# pwm-tl494-smd.net
KiCad netlist of a schematic drawn in Altium Designer
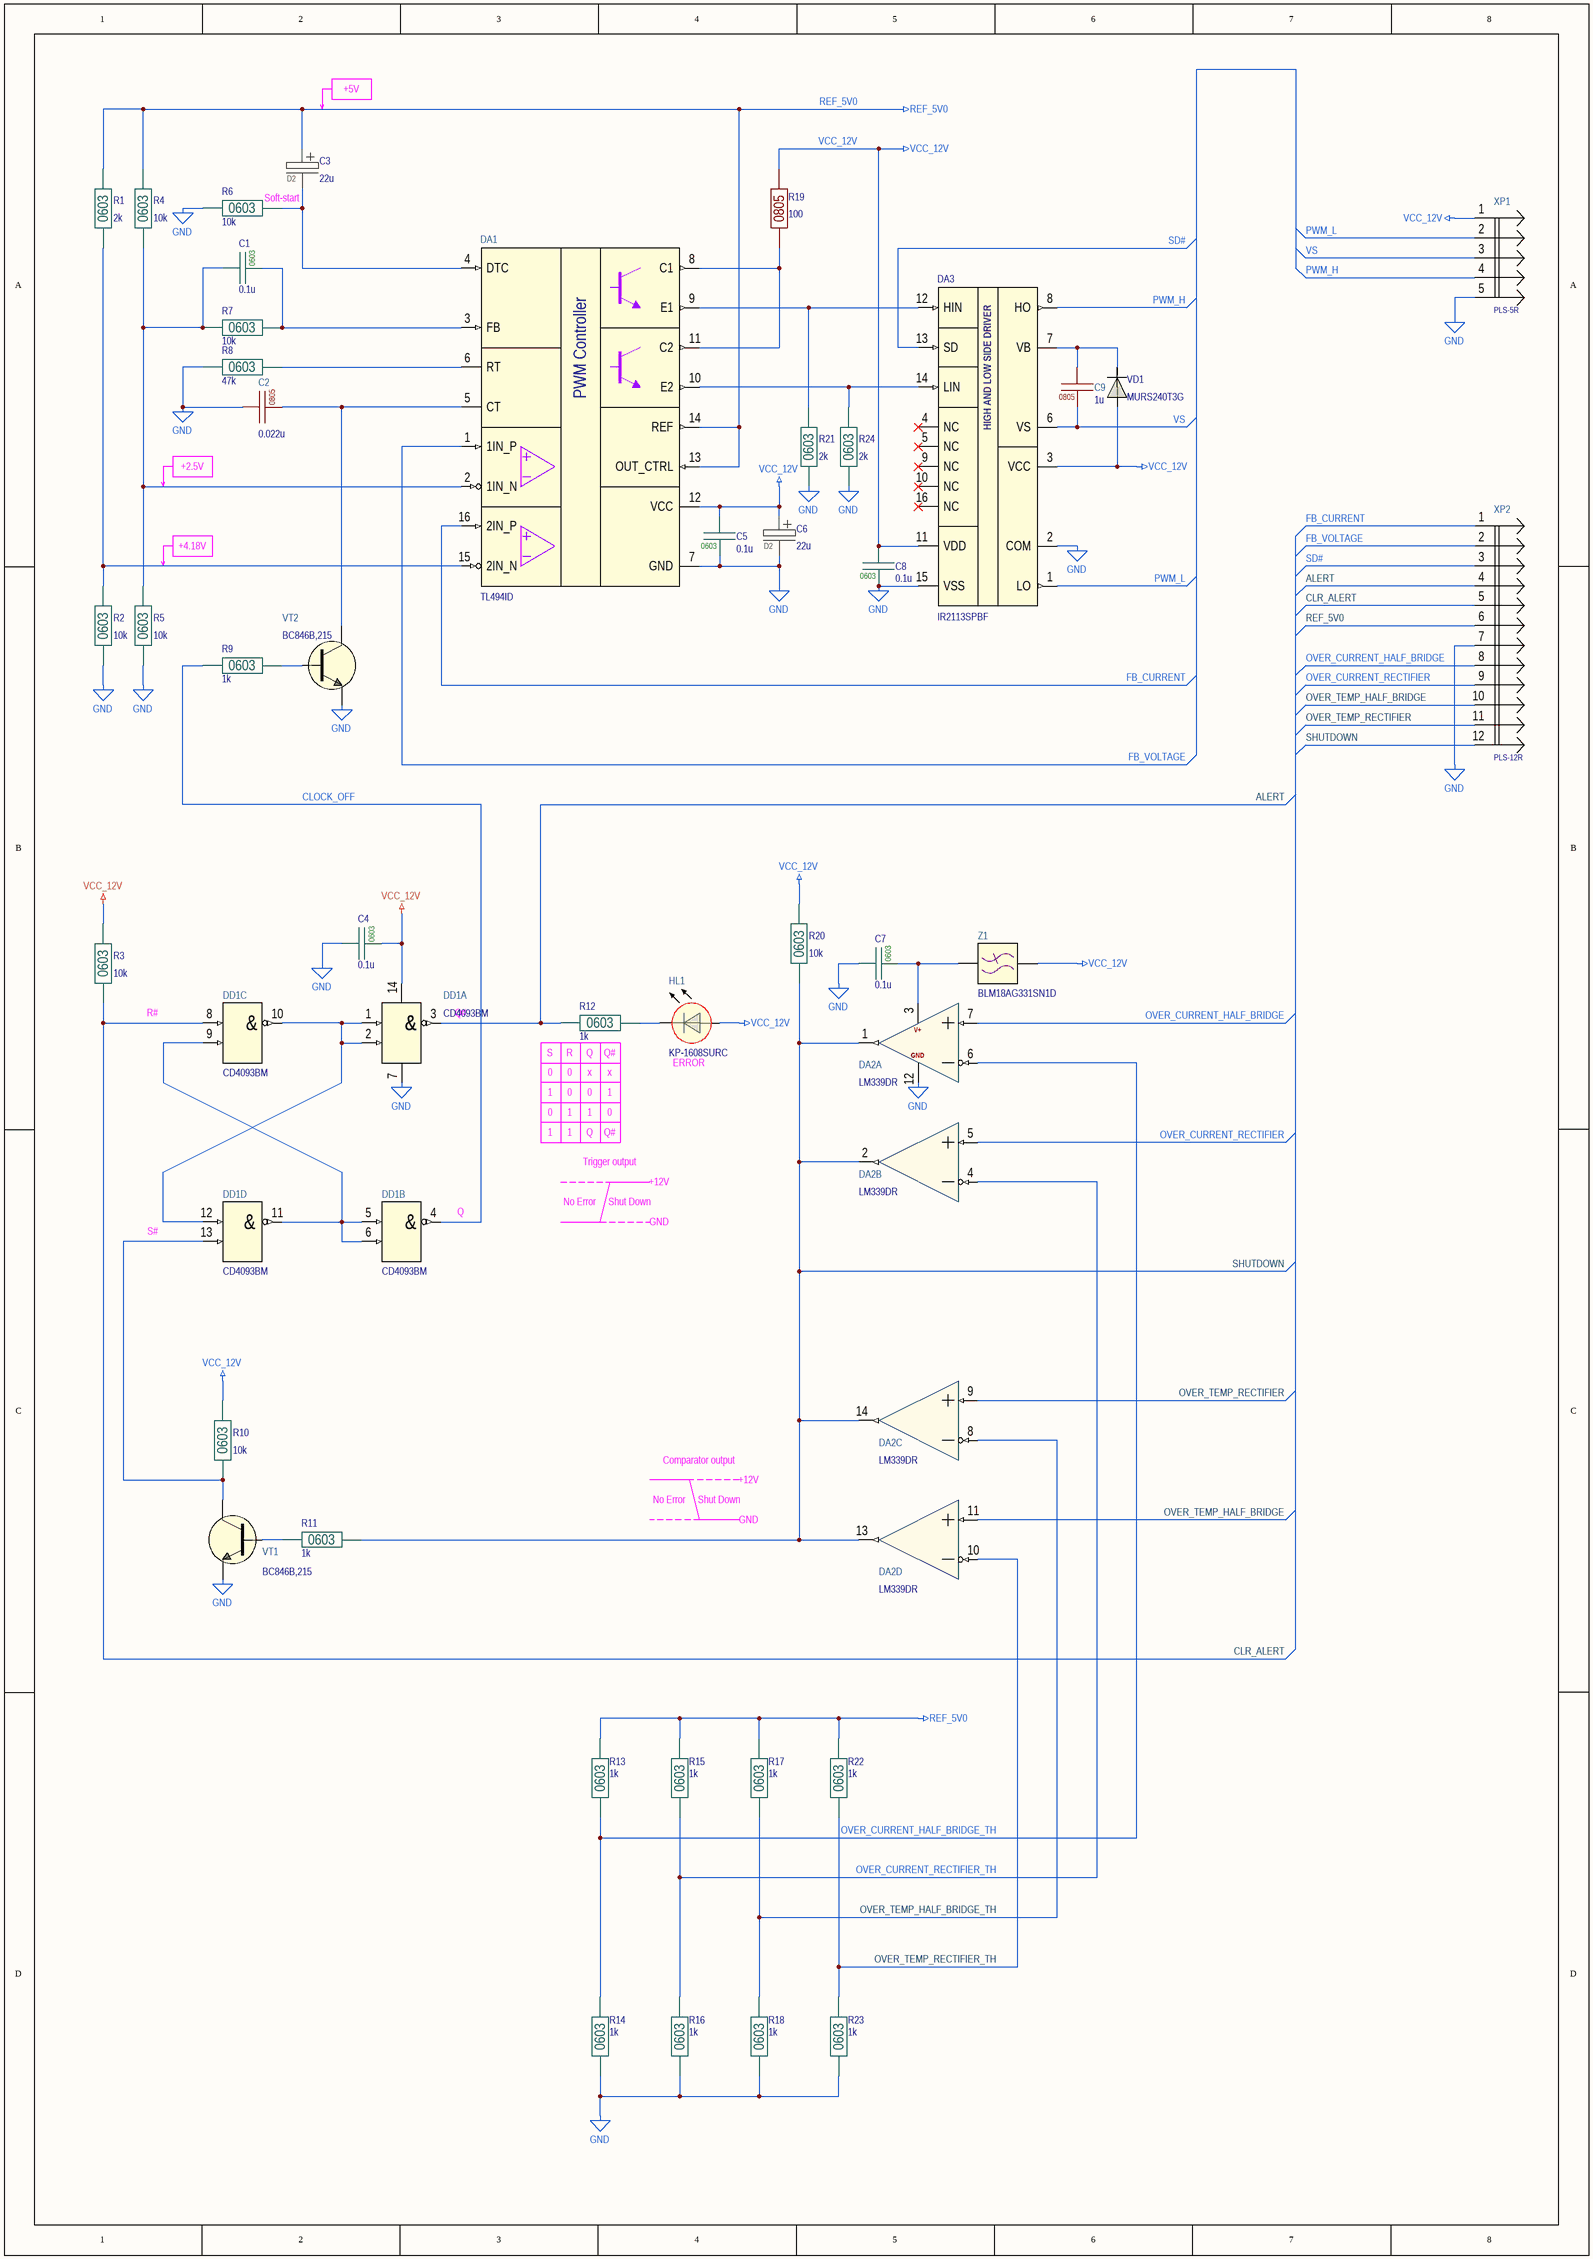
[diagram p0: pwm-tl494-smd.SchDoc]

(export (version "E")
  (design (tool "Eeschema 10.0.6"))
  (components
    (comp (ref "C1")
      (value "0.1u")
      (footprint "PcbLib_RC:CAP0603")
      (description "Capacitors 0603 package case")
      (fields
        (field (name "TOLERANCE") "± 10 %")
        (field (name "VOLTAGE") "50V")
        (field (name "PACKAGE") "0603")
      )
      (libsource (lib "Schlib_RC") (part "C0603"))
    )
    (comp (ref "C2")
      (value "0.022u")
      (footprint "PcbLib_RC:CAP0805-0.95")
      (description "Capacitors 0805 package case")
      (fields
        (field (name "TOLERANCE") "± 5 %")
        (field (name "VOLTAGE") "50V")
        (field (name "PACKAGE") "0805")
      )
      (libsource (lib "Schlib_RC") (part "C0805"))
    )
    (comp (ref "C3")
      (value "22u")
      (footprint "PcbLib_RC:CAP_TQC_D2")
      (description "Conductive Polymer Tantalum Solid Capacitors TQC-Series. Case code D2")
      (fields
        (field (name "TOLERANCE") "± 20 %")
        (field (name "PART NUMBER") "25TQC22MV")
        (field (name "PACKAGE") "D2")
      )
      (libsource (lib "Schlib_RC") (part "C_TQC_D2"))
    )
    (comp (ref "C4")
      (value "0.1u")
      (footprint "PcbLib_RC:CAP0603")
      (description "Capacitors 0603 package case")
      (fields
        (field (name "TOLERANCE") "± 10 %")
        (field (name "VOLTAGE") "50V")
        (field (name "PACKAGE") "0603")
      )
      (libsource (lib "Schlib_RC") (part "C0603"))
    )
    (comp (ref "C5")
      (value "0.1u")
      (footprint "PcbLib_RC:CAP0603")
      (description "Capacitors 0603 package case")
      (fields
        (field (name "TOLERANCE") "± 10 %")
        (field (name "VOLTAGE") "50V")
        (field (name "PACKAGE") "0603")
      )
      (libsource (lib "Schlib_RC") (part "C0603"))
    )
    (comp (ref "C6")
      (value "22u")
      (footprint "PcbLib_RC:CAP_TQC_D2")
      (description "Conductive Polymer Tantalum Solid Capacitors TQC-Series. Case code D2")
      (fields
        (field (name "TOLERANCE") "± 20 %")
        (field (name "PART NUMBER") "25TQC22MV")
        (field (name "PACKAGE") "D2")
      )
      (libsource (lib "Schlib_RC") (part "C_TQC_D2"))
    )
    (comp (ref "C7")
      (value "0.1u")
      (footprint "PcbLib_RC:CAP0603")
      (description "Capacitors 0603 package case")
      (fields
        (field (name "TOLERANCE") "± 10 %")
        (field (name "VOLTAGE") "50V")
        (field (name "PACKAGE") "0603")
      )
      (libsource (lib "Schlib_RC") (part "C0603"))
    )
    (comp (ref "C8")
      (value "0.1u")
      (footprint "PcbLib_RC:CAP0603")
      (description "Capacitors 0603 package case")
      (fields
        (field (name "TOLERANCE") "± 10 %")
        (field (name "VOLTAGE") "50V")
        (field (name "PACKAGE") "0603")
      )
      (libsource (lib "Schlib_RC") (part "C0603"))
    )
    (comp (ref "C9")
      (value "1u")
      (footprint "PcbLib_RC:CAP0805-1.35")
      (description "Capacitors 0805 package case")
      (fields
        (field (name "TOLERANCE") "± 10 %")
        (field (name "VOLTAGE") "50V")
        (field (name "PACKAGE") "0805")
      )
      (libsource (lib "Schlib_RC") (part "C0805"))
    )
    (comp (ref "DA1")
      (value "TL494ID")
      (footprint "PcbLib_ICs:SOIC-16")
      (description "Pulse-Width-Modulation Control Circuits")
      (fields (field (name "MANUFACTURER") "Texas Instruments"))
      (libsource (lib "Schlib_Texas_Instruments") (part "TL494ID"))
    )
    (comp (ref "DA2")
      (value "LM339DR")
      (footprint "PcbLib_ICs:SOIC-14")
      (description "Quad Comparators")
      (fields (field (name "MANUFACTURER") "Texas Instruments"))
      (libsource (lib "Schlib_Texas_Instruments") (part "LM339DR"))
    )
    (comp (ref "DA3")
      (value "IR2113SPBF")
      (footprint "PcbLib_ICs:SO-16W")
      (description "HIGH AND LOW SIDE DRIVER")
      (fields (field (name "MANUFACTURER") "International Rectifier"))
      (libsource (lib "Schlib_Infineon") (part "IR2113SPBF"))
    )
    (comp (ref "DD1")
      (value "CD4093BM")
      (footprint "PcbLib_ICs:SOIC-14")
      (description "Quad 2-Input NAND Gate Schmitt Triggers")
      (fields (field (name "MANUFACTURER") "Texas Instruments"))
      (libsource (lib "Schlib_Texas_Instruments") (part "CD4093BM"))
    )
    (comp (ref "HL1")
      (value "KP-1608SURC")
      (footprint "PcbLib_Others:LED0603R")
      (description "Hyper red led (package case 0603)")
      (fields (field (name "MANUFACTURER") "Kingbright Company LLC."))
      (libsource (lib "Schlib_Kingbright") (part "KP-1608SURC"))
    )
    (comp (ref "R1")
      (value "2k")
      (footprint "PcbLib_RC:RES0603B")
      (description "Resistor 0603 package case")
      (fields
        (field (name "TOLERANCE") "± 1 %")
        (field (name "PART NUMBER") "RC0603FR-072KL")
        (field (name "PACKAGE") "0603")
      )
      (libsource (lib "Schlib_RC") (part "R0603"))
    )
    (comp (ref "R2")
      (value "10k")
      (footprint "PcbLib_RC:RES0603B")
      (description "Resistor 0603 package case")
      (fields
        (field (name "TOLERANCE") "± 1 %")
        (field (name "PART NUMBER") "RC0603FR-0710KL")
        (field (name "PACKAGE") "0603")
      )
      (libsource (lib "Schlib_RC") (part "R0603"))
    )
    (comp (ref "R3")
      (value "10k")
      (footprint "PcbLib_RC:RES0603B")
      (description "Resistor 0603 package case")
      (fields
        (field (name "TOLERANCE") "± 1 %")
        (field (name "PART NUMBER") "RC0603FR-0710KL")
        (field (name "PACKAGE") "0603")
      )
      (libsource (lib "Schlib_RC") (part "R0603"))
    )
    (comp (ref "R4")
      (value "10k")
      (footprint "PcbLib_RC:RES0603B")
      (description "Resistor 0603 package case")
      (fields
        (field (name "TOLERANCE") "± 1 %")
        (field (name "PART NUMBER") "RC0603FR-0710KL")
        (field (name "PACKAGE") "0603")
      )
      (libsource (lib "Schlib_RC") (part "R0603"))
    )
    (comp (ref "R5")
      (value "10k")
      (footprint "PcbLib_RC:RES0603B")
      (description "Resistor 0603 package case")
      (fields
        (field (name "TOLERANCE") "± 1 %")
        (field (name "PART NUMBER") "RC0603FR-0710KL")
        (field (name "PACKAGE") "0603")
      )
      (libsource (lib "Schlib_RC") (part "R0603"))
    )
    (comp (ref "R6")
      (value "10k")
      (footprint "PcbLib_RC:RES0603B")
      (description "Resistor 0603 package case")
      (fields
        (field (name "TOLERANCE") "± 1 %")
        (field (name "PART NUMBER") "RC0603FR-0710KL")
        (field (name "PACKAGE") "0603")
      )
      (libsource (lib "Schlib_RC") (part "R0603"))
    )
    (comp (ref "R7")
      (value "10k")
      (footprint "PcbLib_RC:RES0603B")
      (description "Resistor 0603 package case")
      (fields
        (field (name "TOLERANCE") "± 1 %")
        (field (name "PART NUMBER") "RC0603FR-0710KL")
        (field (name "PACKAGE") "0603")
      )
      (libsource (lib "Schlib_RC") (part "R0603"))
    )
    (comp (ref "R8")
      (value "47k")
      (footprint "PcbLib_RC:RES0603B")
      (description "Resistor 0603 package case")
      (fields
        (field (name "TOLERANCE") "± 1 %")
        (field (name "PART NUMBER") "RC0603FR-0747KL")
        (field (name "PACKAGE") "0603")
      )
      (libsource (lib "Schlib_RC") (part "R0603"))
    )
    (comp (ref "R9")
      (value "1k")
      (footprint "PcbLib_RC:RES0603B")
      (description "Resistor 0603 package case")
      (fields
        (field (name "TOLERANCE") "± 1 %")
        (field (name "PART NUMBER") "RC0603FR-071KL")
        (field (name "PACKAGE") "0603")
      )
      (libsource (lib "Schlib_RC") (part "R0603"))
    )
    (comp (ref "R10")
      (value "10k")
      (footprint "PcbLib_RC:RES0603B")
      (description "Resistor 0603 package case")
      (fields
        (field (name "TOLERANCE") "± 1 %")
        (field (name "PART NUMBER") "RC0603FR-0710KL")
        (field (name "PACKAGE") "0603")
      )
      (libsource (lib "Schlib_RC") (part "R0603"))
    )
    (comp (ref "R11")
      (value "1k")
      (footprint "PcbLib_RC:RES0603B")
      (description "Resistor 0603 package case")
      (fields
        (field (name "TOLERANCE") "± 1 %")
        (field (name "PART NUMBER") "RC0603FR-071KL")
        (field (name "PACKAGE") "0603")
      )
      (libsource (lib "Schlib_RC") (part "R0603"))
    )
    (comp (ref "R12")
      (value "1k")
      (footprint "PcbLib_RC:RES0603B")
      (description "Resistor 0603 package case")
      (fields
        (field (name "TOLERANCE") "± 1 %")
        (field (name "PART NUMBER") "RC0603FR-071KL")
        (field (name "PACKAGE") "0603")
      )
      (libsource (lib "Schlib_RC") (part "R0603"))
    )
    (comp (ref "R13")
      (value "1k")
      (footprint "PcbLib_RC:RES0603B")
      (description "Resistor 0603 package case")
      (fields
        (field (name "TOLERANCE") "± 1 %")
        (field (name "PART NUMBER") "RC0603FR-071KL")
        (field (name "PACKAGE") "0603")
      )
      (libsource (lib "Schlib_RC") (part "R0603"))
    )
    (comp (ref "R14")
      (value "1k")
      (footprint "PcbLib_RC:RES0603B")
      (description "Resistor 0603 package case")
      (fields
        (field (name "TOLERANCE") "± 1 %")
        (field (name "PART NUMBER") "RC0603FR-071KL")
        (field (name "PACKAGE") "0603")
      )
      (libsource (lib "Schlib_RC") (part "R0603"))
    )
    (comp (ref "R15")
      (value "1k")
      (footprint "PcbLib_RC:RES0603B")
      (description "Resistor 0603 package case")
      (fields
        (field (name "TOLERANCE") "± 1 %")
        (field (name "PART NUMBER") "RC0603FR-071KL")
        (field (name "PACKAGE") "0603")
      )
      (libsource (lib "Schlib_RC") (part "R0603"))
    )
    (comp (ref "R16")
      (value "1k")
      (footprint "PcbLib_RC:RES0603B")
      (description "Resistor 0603 package case")
      (fields
        (field (name "TOLERANCE") "± 1 %")
        (field (name "PART NUMBER") "RC0603FR-071KL")
        (field (name "PACKAGE") "0603")
      )
      (libsource (lib "Schlib_RC") (part "R0603"))
    )
    (comp (ref "R17")
      (value "1k")
      (footprint "PcbLib_RC:RES0603B")
      (description "Resistor 0603 package case")
      (fields
        (field (name "TOLERANCE") "± 1 %")
        (field (name "PART NUMBER") "RC0603FR-071KL")
        (field (name "PACKAGE") "0603")
      )
      (libsource (lib "Schlib_RC") (part "R0603"))
    )
    (comp (ref "R18")
      (value "1k")
      (footprint "PcbLib_RC:RES0603B")
      (description "Resistor 0603 package case")
      (fields
        (field (name "TOLERANCE") "± 1 %")
        (field (name "PART NUMBER") "RC0603FR-071KL")
        (field (name "PACKAGE") "0603")
      )
      (libsource (lib "Schlib_RC") (part "R0603"))
    )
    (comp (ref "R19")
      (value "100")
      (footprint "PcbLib_RC:RES0805B")
      (description "Resistor 0805 package case")
      (fields
        (field (name "TOLERANCE") "± 1 %")
        (field (name "PART NUMBER") "RC0805FR-07100RL")
        (field (name "PACKAGE") "0805")
      )
      (libsource (lib "Schlib_RC") (part "R0805"))
    )
    (comp (ref "R20")
      (value "10k")
      (footprint "PcbLib_RC:RES0603B")
      (description "Resistor 0603 package case")
      (fields
        (field (name "TOLERANCE") "± 1 %")
        (field (name "PART NUMBER") "RC0603FR-0710KL")
        (field (name "PACKAGE") "0603")
      )
      (libsource (lib "Schlib_RC") (part "R0603"))
    )
    (comp (ref "R21")
      (value "2k")
      (footprint "PcbLib_RC:RES0603B")
      (description "Resistor 0603 package case")
      (fields
        (field (name "TOLERANCE") "± 1 %")
        (field (name "PART NUMBER") "RC0603FR-072KL")
        (field (name "PACKAGE") "0603")
      )
      (libsource (lib "Schlib_RC") (part "R0603"))
    )
    (comp (ref "R22")
      (value "1k")
      (footprint "PcbLib_RC:RES0603B")
      (description "Resistor 0603 package case")
      (fields
        (field (name "TOLERANCE") "± 1 %")
        (field (name "PART NUMBER") "RC0603FR-071KL")
        (field (name "PACKAGE") "0603")
      )
      (libsource (lib "Schlib_RC") (part "R0603"))
    )
    (comp (ref "R23")
      (value "1k")
      (footprint "PcbLib_RC:RES0603B")
      (description "Resistor 0603 package case")
      (fields
        (field (name "TOLERANCE") "± 1 %")
        (field (name "PART NUMBER") "RC0603FR-071KL")
        (field (name "PACKAGE") "0603")
      )
      (libsource (lib "Schlib_RC") (part "R0603"))
    )
    (comp (ref "R24")
      (value "2k")
      (footprint "PcbLib_RC:RES0603B")
      (description "Resistor 0603 package case")
      (fields
        (field (name "TOLERANCE") "± 1 %")
        (field (name "PART NUMBER") "RC0603FR-072KL")
        (field (name "PACKAGE") "0603")
      )
      (libsource (lib "Schlib_RC") (part "R0603"))
    )
    (comp (ref "VD1")
      (value "MURS240T3G")
      (footprint "PcbLib_Discrete:SMB")
      (description "Diode 400V, 2A")
      (fields (field (name "MANUFACTURER") "ON Semiconductor"))
      (libsource (lib "Schlib_ONSemiconductor") (part "MURS240T3G"))
    )
    (comp (ref "VT1")
      (value "BC846B,215")
      (footprint "PcbLib_ICs:SOT23-3")
      (description "General Purpose n-p-n Transistors")
      (fields (field (name "MANUFACTURER") "Nexperia USA Inc."))
      (libsource (lib "Schlib_NXP_Semiconductors") (part "BC846B,215"))
    )
    (comp (ref "VT2")
      (value "BC846B,215")
      (footprint "PcbLib_ICs:SOT23-3")
      (description "General Purpose n-p-n Transistors")
      (fields (field (name "MANUFACTURER") "Nexperia USA Inc."))
      (libsource (lib "Schlib_NXP_Semiconductors") (part "BC846B,215"))
    )
    (comp (ref "XP1")
      (value "PLS-5R")
      (footprint "PcbLib_Pin_Headers:PLS-5R")
      (libsource (lib "Schlib_Pin_Headers") (part "PLS-5R"))
    )
    (comp (ref "XP2")
      (value "PLS-12R")
      (footprint "PcbLib_Pin_Headers:PLS-12R")
      (libsource (lib "Schlib_Pin_Headers") (part "PLS-12R"))
    )
    (comp (ref "Z1")
      (value "BLM18AG331SN1D")
      (footprint "PcbLib_RC:BLM0603P")
      (description "Power line filter, imperdance 330 Ohm (current 05A)")
      (libsource (lib "Schlib_Murata") (part "BLM18AG331SN1D"))
    )
  )
  (nets
    (net (code "1") (name "/ALERT") (class "Default")
      (node (ref "DD1") (pin "3") (pinfunction "Y0_3") (pintype "output"))
      (node (ref "R12") (pin "2") (pinfunction "2_2") (pintype "passive"))
      (node (ref "XP2") (pin "4") (pinfunction "4_4") (pintype "passive"))
    )
    (net (code "2") (name "/CLOCK_OFF") (class "Default")
      (node (ref "DD1") (pin "4") (pinfunction "Y1_4") (pintype "output"))
      (node (ref "R9") (pin "2") (pinfunction "2_2") (pintype "passive"))
    )
    (net (code "3") (name "/CLR_ALERT") (class "Default")
      (node (ref "DD1") (pin "8") (pinfunction "A2_8") (pintype "input"))
      (node (ref "R3") (pin "1") (pinfunction "1_1") (pintype "passive"))
      (node (ref "XP2") (pin "5") (pinfunction "5_5") (pintype "passive"))
    )
    (net (code "4") (name "/FB_CURRENT") (class "Default")
      (node (ref "DA1") (pin "16") (pinfunction "2IN_P_16") (pintype "input"))
      (node (ref "XP2") (pin "1") (pinfunction "1_1") (pintype "passive"))
    )
    (net (code "5") (name "/FB_VOLTAGE") (class "Default")
      (node (ref "DA1") (pin "1") (pinfunction "1IN_P_1") (pintype "input"))
      (node (ref "XP2") (pin "2") (pinfunction "2_2") (pintype "passive"))
    )
    (net (code "6") (name "/OVER_CURRENT_HALF_BRIDGE") (class "Default")
      (node (ref "DA2") (pin "7") (pinfunction "1IN+_7") (pintype "input"))
      (node (ref "XP2") (pin "8") (pinfunction "8_8") (pintype "passive"))
    )
    (net (code "7") (name "/OVER_CURRENT_HALF_BRIDGE_TH") (class "Default")
      (node (ref "DA2") (pin "6") (pinfunction "1IN-_6") (pintype "input"))
      (node (ref "R13") (pin "2") (pinfunction "2_2") (pintype "passive"))
      (node (ref "R14") (pin "1") (pinfunction "1_1") (pintype "passive"))
    )
    (net (code "8") (name "/OVER_CURRENT_RECTIFIER") (class "Default")
      (node (ref "DA2") (pin "5") (pinfunction "2IN+_5") (pintype "input"))
      (node (ref "XP2") (pin "9") (pinfunction "9_9") (pintype "passive"))
    )
    (net (code "9") (name "/OVER_CURRENT_RECTIFIER_TH") (class "Default")
      (node (ref "DA2") (pin "4") (pinfunction "2IN-_4") (pintype "input"))
      (node (ref "R15") (pin "2") (pinfunction "2_2") (pintype "passive"))
      (node (ref "R16") (pin "1") (pinfunction "1_1") (pintype "passive"))
    )
    (net (code "10") (name "/OVER_TEMP_HALF_BRIDGE") (class "Default")
      (node (ref "DA2") (pin "11") (pinfunction "4IN+_11") (pintype "input"))
      (node (ref "XP2") (pin "10") (pinfunction "10_10") (pintype "passive"))
    )
    (net (code "11") (name "/OVER_TEMP_HALF_BRIDGE_TH") (class "Default")
      (node (ref "DA2") (pin "8") (pinfunction "3IN-_8") (pintype "input"))
      (node (ref "R17") (pin "2") (pinfunction "2_2") (pintype "passive"))
      (node (ref "R18") (pin "1") (pinfunction "1_1") (pintype "passive"))
    )
    (net (code "12") (name "/OVER_TEMP_RECTIFIER") (class "Default")
      (node (ref "DA2") (pin "9") (pinfunction "3IN+_9") (pintype "input"))
      (node (ref "XP2") (pin "11") (pinfunction "11_11") (pintype "passive"))
    )
    (net (code "13") (name "/OVER_TEMP_RECTIFIER_TH") (class "Default")
      (node (ref "DA2") (pin "10") (pinfunction "4IN-_10") (pintype "input"))
      (node (ref "R22") (pin "2") (pinfunction "2_2") (pintype "passive"))
      (node (ref "R23") (pin "1") (pinfunction "1_1") (pintype "passive"))
    )
    (net (code "14") (name "/PWM_H") (class "Default")
      (node (ref "DA3") (pin "8") (pinfunction "HO_8") (pintype "output"))
      (node (ref "XP1") (pin "4") (pinfunction "4_4") (pintype "passive"))
    )
    (net (code "15") (name "/PWM_L") (class "Default")
      (node (ref "DA3") (pin "1") (pinfunction "LO_1") (pintype "output"))
      (node (ref "XP1") (pin "2") (pinfunction "2_2") (pintype "passive"))
    )
    (net (code "16") (name "/SD#") (class "Default")
      (node (ref "DA3") (pin "13") (pinfunction "SD_13") (pintype "input"))
      (node (ref "XP2") (pin "3") (pinfunction "3_3") (pintype "passive"))
    )
    (net (code "17") (name "/SHUTDOWN") (class "Default")
      (node (ref "DA2") (pin "1") (pinfunction "1OUT_1") (pintype "output"))
      (node (ref "DA2") (pin "13") (pinfunction "4OUT_13") (pintype "output"))
      (node (ref "DA2") (pin "14") (pinfunction "3OUT_14") (pintype "output"))
      (node (ref "DA2") (pin "2") (pinfunction "2OUT_2") (pintype "output"))
      (node (ref "R11") (pin "1") (pinfunction "1_1") (pintype "passive"))
      (node (ref "R20") (pin "1") (pinfunction "1_1") (pintype "passive"))
      (node (ref "XP2") (pin "12") (pinfunction "12_12") (pintype "passive"))
    )
    (net (code "18") (name "/VS") (class "Default")
      (node (ref "C9") (pin "1") (pinfunction "1_1") (pintype "passive"))
      (node (ref "DA3") (pin "6") (pinfunction "VS_6") (pintype "power_in"))
      (node (ref "XP1") (pin "3") (pinfunction "3_3") (pintype "passive"))
    )
    (net (code "19") (name "GND") (class "Default")
      (node (ref "C2") (pin "1") (pinfunction "1_1") (pintype "passive"))
      (node (ref "C4") (pin "2") (pinfunction "2_2") (pintype "passive"))
      (node (ref "C5") (pin "1") (pinfunction "1_1") (pintype "passive"))
      (node (ref "C6") (pin "2") (pinfunction "2_2") (pintype "passive"))
      (node (ref "C7") (pin "2") (pinfunction "2_2") (pintype "passive"))
      (node (ref "C8") (pin "1") (pinfunction "1_1") (pintype "passive"))
      (node (ref "DA1") (pin "7") (pinfunction "GND_7") (pintype "power_in"))
      (node (ref "DA2") (pin "12") (pinfunction "GND_12") (pintype "power_in"))
      (node (ref "DA3") (pin "15") (pinfunction "VSS_15") (pintype "power_in"))
      (node (ref "DA3") (pin "2") (pinfunction "COM_2") (pintype "power_in"))
      (node (ref "DD1") (pin "7") (pinfunction "GND_7") (pintype "power_in"))
      (node (ref "R14") (pin "2") (pinfunction "2_2") (pintype "passive"))
      (node (ref "R16") (pin "2") (pinfunction "2_2") (pintype "passive"))
      (node (ref "R18") (pin "2") (pinfunction "2_2") (pintype "passive"))
      (node (ref "R2") (pin "1") (pinfunction "1_1") (pintype "passive"))
      (node (ref "R21") (pin "1") (pinfunction "1_1") (pintype "passive"))
      (node (ref "R23") (pin "2") (pinfunction "2_2") (pintype "passive"))
      (node (ref "R24") (pin "1") (pinfunction "1_1") (pintype "passive"))
      (node (ref "R5") (pin "1") (pinfunction "1_1") (pintype "passive"))
      (node (ref "R6") (pin "2") (pinfunction "2_2") (pintype "passive"))
      (node (ref "R8") (pin "2") (pinfunction "2_2") (pintype "passive"))
      (node (ref "VT1") (pin "2") (pinfunction "E_2") (pintype "passive"))
      (node (ref "VT2") (pin "2") (pinfunction "E_2") (pintype "passive"))
      (node (ref "XP1") (pin "5") (pinfunction "5_5") (pintype "passive"))
      (node (ref "XP2") (pin "7") (pinfunction "7_7") (pintype "passive"))
    )
    (net (code "20") (name "Net-(DA1-1IN_N)") (class "Default")
      (node (ref "C1") (pin "2") (pinfunction "2_2") (pintype "passive"))
      (node (ref "DA1") (pin "2") (pinfunction "1IN_N_2") (pintype "input"))
      (node (ref "R4") (pin "1") (pinfunction "1_1") (pintype "passive"))
      (node (ref "R5") (pin "2") (pinfunction "2_2") (pintype "passive"))
      (node (ref "R7") (pin "2") (pinfunction "2_2") (pintype "passive"))
    )
    (net (code "21") (name "Net-(DA1-2IN_N)") (class "Default")
      (node (ref "DA1") (pin "15") (pinfunction "2IN_N_15") (pintype "input"))
      (node (ref "R1") (pin "1") (pinfunction "1_1") (pintype "passive"))
      (node (ref "R2") (pin "2") (pinfunction "2_2") (pintype "passive"))
    )
    (net (code "22") (name "Net-(DA1-C1)") (class "Default")
      (node (ref "DA1") (pin "11") (pinfunction "C2_11") (pintype "output"))
      (node (ref "DA1") (pin "8") (pinfunction "C1_8") (pintype "output"))
      (node (ref "R19") (pin "1") (pinfunction "1_1") (pintype "passive"))
    )
    (net (code "23") (name "Net-(DA1-CT)") (class "Default")
      (node (ref "C2") (pin "2") (pinfunction "2_2") (pintype "passive"))
      (node (ref "DA1") (pin "5") (pinfunction "CT_5") (pintype "passive"))
      (node (ref "VT2") (pin "3") (pinfunction "C_3") (pintype "passive"))
    )
    (net (code "24") (name "Net-(DA1-DTC)") (class "Default")
      (node (ref "C3") (pin "2") (pinfunction "2_2") (pintype "passive"))
      (node (ref "DA1") (pin "4") (pinfunction "DTC_4") (pintype "input"))
      (node (ref "R6") (pin "1") (pinfunction "1_1") (pintype "passive"))
    )
    (net (code "25") (name "Net-(DA1-E1)") (class "Default")
      (node (ref "DA1") (pin "9") (pinfunction "E1_9") (pintype "output"))
      (node (ref "DA3") (pin "12") (pinfunction "HIN_12") (pintype "input"))
      (node (ref "R21") (pin "2") (pinfunction "2_2") (pintype "passive"))
    )
    (net (code "26") (name "Net-(DA1-E2)") (class "Default")
      (node (ref "DA1") (pin "10") (pinfunction "E2_10") (pintype "output"))
      (node (ref "DA3") (pin "14") (pinfunction "LIN_14") (pintype "input"))
      (node (ref "R24") (pin "2") (pinfunction "2_2") (pintype "passive"))
    )
    (net (code "27") (name "Net-(DA1-FB)") (class "Default")
      (node (ref "C1") (pin "1") (pinfunction "1_1") (pintype "passive"))
      (node (ref "DA1") (pin "3") (pinfunction "FB_3") (pintype "input"))
      (node (ref "R7") (pin "1") (pinfunction "1_1") (pintype "passive"))
    )
    (net (code "28") (name "Net-(DA1-RT)") (class "Default")
      (node (ref "DA1") (pin "6") (pinfunction "RT_6") (pintype "passive"))
      (node (ref "R8") (pin "1") (pinfunction "1_1") (pintype "passive"))
    )
    (net (code "29") (name "Net-(DA2A-VCC)") (class "Default")
      (node (ref "C7") (pin "1") (pinfunction "1_1") (pintype "passive"))
      (node (ref "DA2") (pin "3") (pinfunction "VCC_3") (pintype "power_in"))
      (node (ref "Z1") (pin "1") (pinfunction "1_1") (pintype "passive"))
    )
    (net (code "30") (name "Net-(DA3-VB)") (class "Default")
      (node (ref "C9") (pin "2") (pinfunction "2_2") (pintype "passive"))
      (node (ref "DA3") (pin "7") (pinfunction "VB_7") (pintype "power_in"))
      (node (ref "VD1") (pin "1") (pinfunction "C_1") (pintype "passive"))
    )
    (net (code "31") (name "Net-(DD1A-A0)") (class "Default")
      (node (ref "DD1") (pin "1") (pinfunction "A0_1") (pintype "input"))
      (node (ref "DD1") (pin "10") (pinfunction "Y2_10") (pintype "output"))
      (node (ref "DD1") (pin "12") (pinfunction "A3_12") (pintype "input"))
      (node (ref "DD1") (pin "2") (pinfunction "B0_2") (pintype "input"))
    )
    (net (code "32") (name "Net-(DD1B-A1)") (class "Default")
      (node (ref "DD1") (pin "11") (pinfunction "Y3_11") (pintype "output"))
      (node (ref "DD1") (pin "5") (pinfunction "A1_5") (pintype "input"))
      (node (ref "DD1") (pin "6") (pinfunction "B1_6") (pintype "input"))
      (node (ref "DD1") (pin "9") (pinfunction "B2_9") (pintype "input"))
    )
    (net (code "33") (name "Net-(DD1D-B3)") (class "Default")
      (node (ref "DD1") (pin "13") (pinfunction "B3_13") (pintype "input"))
      (node (ref "R10") (pin "1") (pinfunction "1_1") (pintype "passive"))
      (node (ref "VT1") (pin "3") (pinfunction "C_3") (pintype "passive"))
    )
    (net (code "34") (name "Net-(HL1-Pad1)") (class "Default")
      (node (ref "HL1") (pin "1") (pinfunction "1_1") (pintype "passive"))
      (node (ref "R12") (pin "1") (pinfunction "1_1") (pintype "passive"))
    )
    (net (code "35") (name "Net-(VT1-B)") (class "Default")
      (node (ref "R11") (pin "2") (pinfunction "2_2") (pintype "passive"))
      (node (ref "VT1") (pin "1") (pinfunction "B_1") (pintype "passive"))
    )
    (net (code "36") (name "Net-(VT2-B)") (class "Default")
      (node (ref "R9") (pin "1") (pinfunction "1_1") (pintype "passive"))
      (node (ref "VT2") (pin "1") (pinfunction "B_1") (pintype "passive"))
    )
    (net (code "37") (name "REF_5V0") (class "Default")
      (node (ref "C3") (pin "1") (pinfunction "1_1") (pintype "passive"))
      (node (ref "DA1") (pin "13") (pinfunction "OUT_CTRL_13") (pintype "input"))
      (node (ref "DA1") (pin "14") (pinfunction "REF_14") (pintype "output"))
      (node (ref "R1") (pin "2") (pinfunction "2_2") (pintype "passive"))
      (node (ref "R13") (pin "1") (pinfunction "1_1") (pintype "passive"))
      (node (ref "R15") (pin "1") (pinfunction "1_1") (pintype "passive"))
      (node (ref "R17") (pin "1") (pinfunction "1_1") (pintype "passive"))
      (node (ref "R22") (pin "1") (pinfunction "1_1") (pintype "passive"))
      (node (ref "R4") (pin "2") (pinfunction "2_2") (pintype "passive"))
      (node (ref "XP2") (pin "6") (pinfunction "6_6") (pintype "passive"))
    )
    (net (code "38") (name "VCC_12V") (class "Default")
      (node (ref "C4") (pin "1") (pinfunction "1_1") (pintype "passive"))
      (node (ref "C5") (pin "2") (pinfunction "2_2") (pintype "passive"))
      (node (ref "C6") (pin "1") (pinfunction "1_1") (pintype "passive"))
      (node (ref "C8") (pin "2") (pinfunction "2_2") (pintype "passive"))
      (node (ref "DA1") (pin "12") (pinfunction "VCC_12") (pintype "power_in"))
      (node (ref "DA3") (pin "11") (pinfunction "VDD_11") (pintype "power_in"))
      (node (ref "DA3") (pin "3") (pinfunction "VCC_3") (pintype "power_in"))
      (node (ref "DD1") (pin "14") (pinfunction "VCC_14") (pintype "power_in"))
      (node (ref "HL1") (pin "2") (pinfunction "2_2") (pintype "passive"))
      (node (ref "R10") (pin "2") (pinfunction "2_2") (pintype "passive"))
      (node (ref "R19") (pin "2") (pinfunction "2_2") (pintype "passive"))
      (node (ref "R20") (pin "2") (pinfunction "2_2") (pintype "passive"))
      (node (ref "R3") (pin "2") (pinfunction "2_2") (pintype "passive"))
      (node (ref "VD1") (pin "2") (pinfunction "A_2") (pintype "passive"))
      (node (ref "XP1") (pin "1") (pinfunction "1_1") (pintype "passive"))
      (node (ref "Z1") (pin "2") (pinfunction "2_2") (pintype "passive"))
    )
    (net (code "39") (name "unconnected-(DA3-NC-Pad4)") (class "Default")
      (node (ref "DA3") (pin "4") (pinfunction "NC_4") (pintype "tri_state+no_connect"))
    )
    (net (code "40") (name "unconnected-(DA3-NC-Pad5)") (class "Default")
      (node (ref "DA3") (pin "5") (pinfunction "NC_5") (pintype "tri_state+no_connect"))
    )
    (net (code "41") (name "unconnected-(DA3-NC-Pad9)") (class "Default")
      (node (ref "DA3") (pin "9") (pinfunction "NC_9") (pintype "tri_state+no_connect"))
    )
    (net (code "42") (name "unconnected-(DA3-NC-Pad10)") (class "Default")
      (node (ref "DA3") (pin "10") (pinfunction "NC_10") (pintype "tri_state+no_connect"))
    )
    (net (code "43") (name "unconnected-(DA3-NC-Pad16)") (class "Default")
      (node (ref "DA3") (pin "16") (pinfunction "NC_16") (pintype "tri_state+no_connect"))
    )
  )
)
